# D710-gps.net
KiCad netlist of a schematic drawn in EAGLE
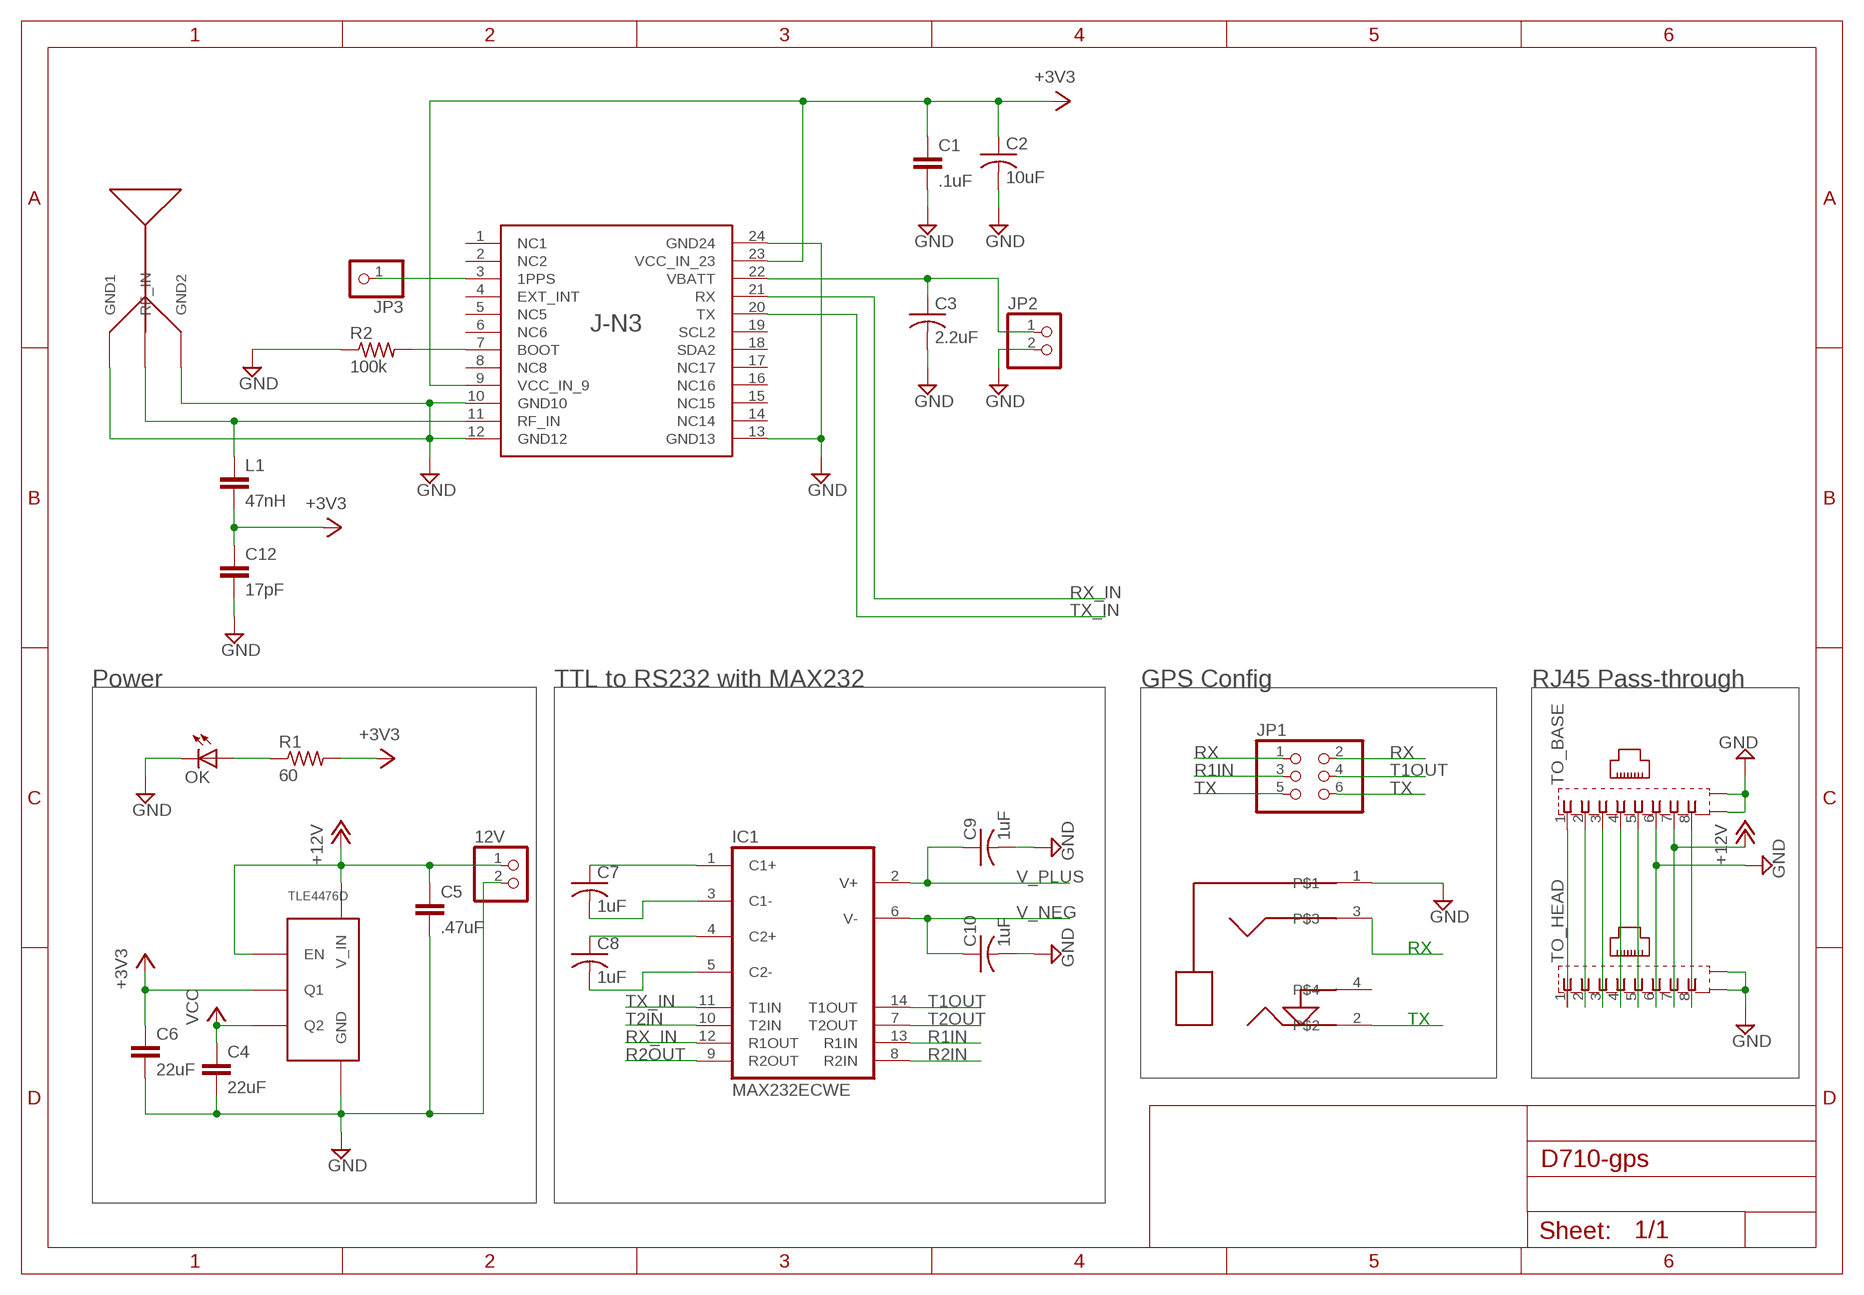
[diagram p0: schematic, sheet 1]

(export (version "E")
  (design (tool "Eeschema 10.0.6"))
  (components
    (comp (ref "12V")
      (value "PINHD-1X2")
      (footprint "eagle-import:1X02")
      (libsource (lib "eagle-import") (part "PINHD-1X2"))
    )
    (comp (ref "ANT")
      (value "GEO_HELIX_GPSANT")
      (footprint "eagle-import:GEO_HELIX_GPSANT")
      (libsource (lib "eagle-import") (part "GEO_HELIX_GPSANT"))
    )
    (comp (ref "C1")
      (value ".1uF")
      (footprint "eagle-import:C0805")
      (libsource (lib "eagle-import") (part "C-EUC0805"))
    )
    (comp (ref "C2")
      (value "10uF")
      (footprint "eagle-import:C0805")
      (fields (field (name "MPN") "06034D106MAT2A"))
      (libsource (lib "eagle-import") (part "C-USC0805"))
    )
    (comp (ref "C3")
      (value "2.2uF")
      (footprint "eagle-import:C0805")
      (libsource (lib "eagle-import") (part "C-USC0805"))
    )
    (comp (ref "C4")
      (value "22uF")
      (footprint "eagle-import:C0805")
      (libsource (lib "eagle-import") (part "C-EUC0805"))
    )
    (comp (ref "C5")
      (value ".47uF")
      (footprint "eagle-import:C0805")
      (libsource (lib "eagle-import") (part "C-EUC0805"))
    )
    (comp (ref "C6")
      (value "22uF")
      (footprint "eagle-import:C0805")
      (libsource (lib "eagle-import") (part "C-EUC0805"))
    )
    (comp (ref "C7")
      (value "1uF")
      (footprint "eagle-import:C0805")
      (fields (field (name "MPN") "02016D105MAT2A"))
      (libsource (lib "eagle-import") (part "C-USC0805"))
    )
    (comp (ref "C8")
      (value "1uF")
      (footprint "eagle-import:C0805")
      (fields (field (name "MPN") "02016D105MAT2A"))
      (libsource (lib "eagle-import") (part "C-USC0805"))
    )
    (comp (ref "C9")
      (value "1uF")
      (footprint "eagle-import:C0805")
      (fields (field (name "MPN") "02016D105MAT2A"))
      (libsource (lib "eagle-import") (part "C-USC0805"))
    )
    (comp (ref "C10")
      (value "1uF")
      (footprint "eagle-import:C0805")
      (fields (field (name "MPN") "02016D105MAT2A"))
      (libsource (lib "eagle-import") (part "C-USC0805"))
    )
    (comp (ref "C12")
      (value "17pF")
      (footprint "eagle-import:C0603")
      (libsource (lib "eagle-import") (part "C-EUC0603"))
    )
    (comp (ref "GPS")
      (value "2.5MM_JACK")
      (footprint "eagle-import:2.5MM_AUDIO")
      (libsource (lib "eagle-import") (part "2.5MM_JACK"))
    )
    (comp (ref "IC1")
      (value "MAX232ECWE")
      (footprint "eagle-import:SO16L")
      (fields (field (name "MF") "MAXIM") (field (name "MPN") "MAX232ECWE+"))
      (libsource (lib "eagle-import") (part "MAX232ECWE"))
    )
    (comp (ref "JP1")
      (value "PINHD-2X3")
      (footprint "eagle-import:2X03")
      (libsource (lib "eagle-import") (part "PINHD-2X3"))
    )
    (comp (ref "JP2")
      (value "PINHD-1X2")
      (footprint "eagle-import:1X02")
      (libsource (lib "eagle-import") (part "PINHD-1X2"))
    )
    (comp (ref "JP3")
      (value "PINHD-1X1")
      (footprint "eagle-import:1X01")
      (libsource (lib "eagle-import") (part "PINHD-1X1"))
    )
    (comp (ref "L1")
      (value "47nH")
      (footprint "eagle-import:C0603")
      (libsource (lib "eagle-import") (part "C-EUC0603"))
    )
    (comp (ref "OK")
      (value "LEDCHIPLED_0805")
      (footprint "eagle-import:CHIPLED_0805")
      (libsource (lib "eagle-import") (part "LEDCHIPLED_0805"))
    )
    (comp (ref "R1")
      (value "60")
      (footprint "eagle-import:R0805")
      (libsource (lib "eagle-import") (part "R-US_R0805"))
    )
    (comp (ref "R2")
      (value "100k")
      (footprint "eagle-import:R0603")
      (libsource (lib "eagle-import") (part "R-US_R0603"))
    )
    (comp (ref "TLE4476D")
      (value "TLE4476D")
      (footprint "eagle-import:TO-252-5")
      (libsource (lib "eagle-import") (part "TLE4476D"))
    )
    (comp (ref "TO_BASE")
      (value "555141-1")
      (footprint "eagle-import:555153-1")
      (libsource (lib "eagle-import") (part "555141-1"))
    )
    (comp (ref "TO_HEAD")
      (value "555141-1")
      (footprint "eagle-import:555153-1")
      (libsource (lib "eagle-import") (part "555141-1"))
    )
    (comp (ref "U$1")
      (value "TELIT_JN3")
      (footprint "eagle-import:24-SMD")
      (libsource (lib "eagle-import") (part "TELIT_JN3"))
    )
  )
  (nets
    (net (code "1") (name "+3V3") (class "Default")
      (node (ref "C1") (pin "1") (pinfunction "1_1") (pintype "passive"))
      (node (ref "C12") (pin "1") (pinfunction "1_1") (pintype "passive"))
      (node (ref "C2") (pin "1") (pinfunction "1_1") (pintype "passive"))
      (node (ref "C6") (pin "1") (pinfunction "1_1") (pintype "passive"))
      (node (ref "L1") (pin "2") (pinfunction "2_2") (pintype "passive"))
      (node (ref "R1") (pin "2") (pinfunction "2_2") (pintype "passive"))
      (node (ref "TLE4476D") (pin "Q1") (pinfunction "Q1_Q1") (pintype "bidirectional"))
      (node (ref "U$1") (pin "23") (pinfunction "VCC_IN_23_23") (pintype "bidirectional"))
      (node (ref "U$1") (pin "9") (pinfunction "VCC_IN_9_9") (pintype "bidirectional"))
    )
    (net (code "2") (name "+12V") (class "Default")
      (node (ref "12V") (pin "1") (pinfunction "1_1") (pintype "passive"))
      (node (ref "C5") (pin "1") (pinfunction "1_1") (pintype "passive"))
      (node (ref "TLE4476D") (pin "EN") (pinfunction "EN_EN") (pintype "bidirectional"))
      (node (ref "TLE4476D") (pin "V_IN") (pinfunction "V_IN_V_IN") (pintype "bidirectional"))
      (node (ref "TO_BASE") (pin "7") (pinfunction "7_7") (pintype "passive"))
      (node (ref "TO_HEAD") (pin "7") (pinfunction "7_7") (pintype "passive"))
    )
    (net (code "3") (name "/R1IN") (class "Default")
      (node (ref "IC1") (pin "13") (pinfunction "R1IN_13") (pintype "input"))
      (node (ref "JP1") (pin "3") (pinfunction "3_3") (pintype "passive"))
    )
    (net (code "4") (name "/R2IN") (class "Default")
      (node (ref "IC1") (pin "8") (pinfunction "R2IN_8") (pintype "input"))
    )
    (net (code "5") (name "/R2OUT") (class "Default")
      (node (ref "IC1") (pin "9") (pinfunction "R2OUT_9") (pintype "output"))
    )
    (net (code "6") (name "/RX") (class "Default")
      (node (ref "GPS") (pin "3") (pinfunction "P$3_3") (pintype "bidirectional"))
      (node (ref "JP1") (pin "1") (pinfunction "1_1") (pintype "passive"))
      (node (ref "JP1") (pin "2") (pinfunction "2_2") (pintype "passive"))
    )
    (net (code "7") (name "/RX_IN") (class "Default")
      (node (ref "IC1") (pin "12") (pinfunction "R1OUT_12") (pintype "output"))
      (node (ref "U$1") (pin "21") (pinfunction "RX_21") (pintype "bidirectional"))
    )
    (net (code "8") (name "/T1OUT") (class "Default")
      (node (ref "IC1") (pin "14") (pinfunction "T1OUT_14") (pintype "output"))
      (node (ref "JP1") (pin "4") (pinfunction "4_4") (pintype "passive"))
    )
    (net (code "9") (name "/T2IN") (class "Default")
      (node (ref "IC1") (pin "10") (pinfunction "T2IN_10") (pintype "input"))
    )
    (net (code "10") (name "/T2OUT") (class "Default")
      (node (ref "IC1") (pin "7") (pinfunction "T2OUT_7") (pintype "output"))
    )
    (net (code "11") (name "/TX") (class "Default")
      (node (ref "GPS") (pin "2") (pinfunction "P$2_2") (pintype "bidirectional"))
      (node (ref "JP1") (pin "5") (pinfunction "5_5") (pintype "passive"))
      (node (ref "JP1") (pin "6") (pinfunction "6_6") (pintype "passive"))
    )
    (net (code "12") (name "/TX_IN") (class "Default")
      (node (ref "IC1") (pin "11") (pinfunction "T1IN_11") (pintype "input"))
      (node (ref "U$1") (pin "20") (pinfunction "TX_20") (pintype "bidirectional"))
    )
    (net (code "13") (name "/V_NEG") (class "Default")
      (node (ref "C10") (pin "1") (pinfunction "1_1") (pintype "passive"))
      (node (ref "IC1") (pin "6") (pinfunction "V-_6") (pintype "bidirectional"))
    )
    (net (code "14") (name "/V_PLUS") (class "Default")
      (node (ref "C9") (pin "1") (pinfunction "1_1") (pintype "passive"))
      (node (ref "IC1") (pin "2") (pinfunction "V+_2") (pintype "bidirectional"))
    )
    (net (code "15") (name "GND") (class "Default")
      (node (ref "12V") (pin "2") (pinfunction "2_2") (pintype "passive"))
      (node (ref "ANT") (pin "GND1") (pinfunction "GND1_GND1") (pintype "bidirectional"))
      (node (ref "ANT") (pin "GND2") (pinfunction "GND2_GND2") (pintype "bidirectional"))
      (node (ref "C1") (pin "2") (pinfunction "2_2") (pintype "passive"))
      (node (ref "C10") (pin "2") (pinfunction "2_2") (pintype "passive"))
      (node (ref "C12") (pin "2") (pinfunction "2_2") (pintype "passive"))
      (node (ref "C2") (pin "2") (pinfunction "2_2") (pintype "passive"))
      (node (ref "C3") (pin "2") (pinfunction "2_2") (pintype "passive"))
      (node (ref "C4") (pin "2") (pinfunction "2_2") (pintype "passive"))
      (node (ref "C5") (pin "2") (pinfunction "2_2") (pintype "passive"))
      (node (ref "C6") (pin "2") (pinfunction "2_2") (pintype "passive"))
      (node (ref "C9") (pin "2") (pinfunction "2_2") (pintype "passive"))
      (node (ref "GPS") (pin "1") (pinfunction "P$1_1") (pintype "bidirectional"))
      (node (ref "JP2") (pin "2") (pinfunction "2_2") (pintype "passive"))
      (node (ref "OK") (pin "C") (pinfunction "C_C") (pintype "passive"))
      (node (ref "R2") (pin "1") (pinfunction "1_1") (pintype "passive"))
      (node (ref "TLE4476D") (pin "GND") (pinfunction "GND_GND") (pintype "bidirectional"))
      (node (ref "TO_BASE") (pin "6") (pinfunction "6_6") (pintype "passive"))
      (node (ref "TO_BASE") (pin "G1") (pinfunction "S1_G1") (pintype "passive"))
      (node (ref "TO_BASE") (pin "G2") (pinfunction "S2_G2") (pintype "passive"))
      (node (ref "TO_HEAD") (pin "6") (pinfunction "6_6") (pintype "passive"))
      (node (ref "TO_HEAD") (pin "G1") (pinfunction "S1_G1") (pintype "passive"))
      (node (ref "TO_HEAD") (pin "G2") (pinfunction "S2_G2") (pintype "passive"))
      (node (ref "U$1") (pin "10") (pinfunction "GND10_10") (pintype "bidirectional"))
      (node (ref "U$1") (pin "12") (pinfunction "GND12_12") (pintype "bidirectional"))
      (node (ref "U$1") (pin "13") (pinfunction "GND13_13") (pintype "bidirectional"))
      (node (ref "U$1") (pin "24") (pinfunction "GND24_24") (pintype "bidirectional"))
    )
    (net (code "16") (name "Net-(IC1A-C1+)") (class "Default")
      (node (ref "C7") (pin "1") (pinfunction "1_1") (pintype "passive"))
      (node (ref "IC1") (pin "1") (pinfunction "C1+_1") (pintype "bidirectional"))
    )
    (net (code "17") (name "Net-(IC1A-C1-)") (class "Default")
      (node (ref "C7") (pin "2") (pinfunction "2_2") (pintype "passive"))
      (node (ref "IC1") (pin "3") (pinfunction "C1-_3") (pintype "bidirectional"))
    )
    (net (code "18") (name "Net-(IC1A-C2+)") (class "Default")
      (node (ref "C8") (pin "1") (pinfunction "1_1") (pintype "passive"))
      (node (ref "IC1") (pin "4") (pinfunction "C2+_4") (pintype "bidirectional"))
    )
    (net (code "19") (name "Net-(IC1A-C2-)") (class "Default")
      (node (ref "C8") (pin "2") (pinfunction "2_2") (pintype "passive"))
      (node (ref "IC1") (pin "5") (pinfunction "C2-_5") (pintype "bidirectional"))
    )
    (net (code "20") (name "Net-(OK-PadA)") (class "Default")
      (node (ref "OK") (pin "A") (pinfunction "A_A") (pintype "passive"))
      (node (ref "R1") (pin "1") (pinfunction "1_1") (pintype "passive"))
    )
    (net (code "21") (name "Net-(TO_BASE-Pad1)") (class "Default")
      (node (ref "TO_BASE") (pin "1") (pinfunction "1_1") (pintype "passive"))
      (node (ref "TO_HEAD") (pin "1") (pinfunction "1_1") (pintype "passive"))
    )
    (net (code "22") (name "Net-(TO_BASE-Pad2)") (class "Default")
      (node (ref "TO_BASE") (pin "2") (pinfunction "2_2") (pintype "passive"))
      (node (ref "TO_HEAD") (pin "2") (pinfunction "2_2") (pintype "passive"))
    )
    (net (code "23") (name "Net-(TO_BASE-Pad3)") (class "Default")
      (node (ref "TO_BASE") (pin "3") (pinfunction "3_3") (pintype "passive"))
      (node (ref "TO_HEAD") (pin "3") (pinfunction "3_3") (pintype "passive"))
    )
    (net (code "24") (name "Net-(TO_BASE-Pad4)") (class "Default")
      (node (ref "TO_BASE") (pin "4") (pinfunction "4_4") (pintype "passive"))
      (node (ref "TO_HEAD") (pin "4") (pinfunction "4_4") (pintype "passive"))
    )
    (net (code "25") (name "Net-(TO_BASE-Pad5)") (class "Default")
      (node (ref "TO_BASE") (pin "5") (pinfunction "5_5") (pintype "passive"))
      (node (ref "TO_HEAD") (pin "5") (pinfunction "5_5") (pintype "passive"))
    )
    (net (code "26") (name "Net-(TO_BASE-Pad8)") (class "Default")
      (node (ref "TO_BASE") (pin "8") (pinfunction "8_8") (pintype "passive"))
      (node (ref "TO_HEAD") (pin "8") (pinfunction "8_8") (pintype "passive"))
    )
    (net (code "27") (name "Net-(U$1-1PPS)") (class "Default")
      (node (ref "JP3") (pin "1") (pinfunction "1_1") (pintype "passive"))
      (node (ref "U$1") (pin "3") (pinfunction "1PPS_3") (pintype "bidirectional"))
    )
    (net (code "28") (name "Net-(U$1-BOOT)") (class "Default")
      (node (ref "R2") (pin "2") (pinfunction "2_2") (pintype "passive"))
      (node (ref "U$1") (pin "7") (pinfunction "BOOT_7") (pintype "bidirectional"))
    )
    (net (code "29") (name "Net-(U$1-RF_IN)") (class "Default")
      (node (ref "ANT") (pin "RF_IN") (pinfunction "RF_IN_RF_IN") (pintype "bidirectional"))
      (node (ref "L1") (pin "1") (pinfunction "1_1") (pintype "passive"))
      (node (ref "U$1") (pin "11") (pinfunction "RF_IN_11") (pintype "bidirectional"))
    )
    (net (code "30") (name "Net-(U$1-VBATT)") (class "Default")
      (node (ref "C3") (pin "1") (pinfunction "1_1") (pintype "passive"))
      (node (ref "JP2") (pin "1") (pinfunction "1_1") (pintype "passive"))
      (node (ref "U$1") (pin "22") (pinfunction "VBATT_22") (pintype "bidirectional"))
    )
    (net (code "31") (name "VCC") (class "Default")
      (node (ref "C4") (pin "1") (pinfunction "1_1") (pintype "passive"))
      (node (ref "TLE4476D") (pin "Q2") (pinfunction "Q2_Q2") (pintype "bidirectional"))
    )
    (net (code "32") (name "unconnected-(GPS-P$4-Pad4)") (class "Default")
      (node (ref "GPS") (pin "4") (pinfunction "P$4_4") (pintype "bidirectional"))
    )
    (net (code "33") (name "unconnected-(U$1-EXT_INT-Pad4)") (class "Default")
      (node (ref "U$1") (pin "4") (pinfunction "EXT_INT_4") (pintype "bidirectional"))
    )
    (net (code "34") (name "unconnected-(U$1-NC1-Pad1)") (class "Default")
      (node (ref "U$1") (pin "1") (pinfunction "NC1_1") (pintype "bidirectional"))
    )
    (net (code "35") (name "unconnected-(U$1-NC2-Pad2)") (class "Default")
      (node (ref "U$1") (pin "2") (pinfunction "NC2_2") (pintype "bidirectional"))
    )
    (net (code "36") (name "unconnected-(U$1-NC5-Pad5)") (class "Default")
      (node (ref "U$1") (pin "5") (pinfunction "NC5_5") (pintype "bidirectional"))
    )
    (net (code "37") (name "unconnected-(U$1-NC6-Pad6)") (class "Default")
      (node (ref "U$1") (pin "6") (pinfunction "NC6_6") (pintype "bidirectional"))
    )
    (net (code "38") (name "unconnected-(U$1-NC8-Pad8)") (class "Default")
      (node (ref "U$1") (pin "8") (pinfunction "NC8_8") (pintype "bidirectional"))
    )
    (net (code "39") (name "unconnected-(U$1-NC14-Pad14)") (class "Default")
      (node (ref "U$1") (pin "14") (pinfunction "NC14_14") (pintype "bidirectional"))
    )
    (net (code "40") (name "unconnected-(U$1-NC15-Pad15)") (class "Default")
      (node (ref "U$1") (pin "15") (pinfunction "NC15_15") (pintype "bidirectional"))
    )
    (net (code "41") (name "unconnected-(U$1-NC16-Pad16)") (class "Default")
      (node (ref "U$1") (pin "16") (pinfunction "NC16_16") (pintype "bidirectional"))
    )
    (net (code "42") (name "unconnected-(U$1-NC17-Pad17)") (class "Default")
      (node (ref "U$1") (pin "17") (pinfunction "NC17_17") (pintype "bidirectional"))
    )
    (net (code "43") (name "unconnected-(U$1-SCL2-Pad19)") (class "Default")
      (node (ref "U$1") (pin "19") (pinfunction "SCL2_19") (pintype "bidirectional"))
    )
    (net (code "44") (name "unconnected-(U$1-SDA2-Pad18)") (class "Default")
      (node (ref "U$1") (pin "18") (pinfunction "SDA2_18") (pintype "bidirectional"))
    )
  )
)
